# MCU.net
KiCad netlist of a schematic drawn in Altium Designer
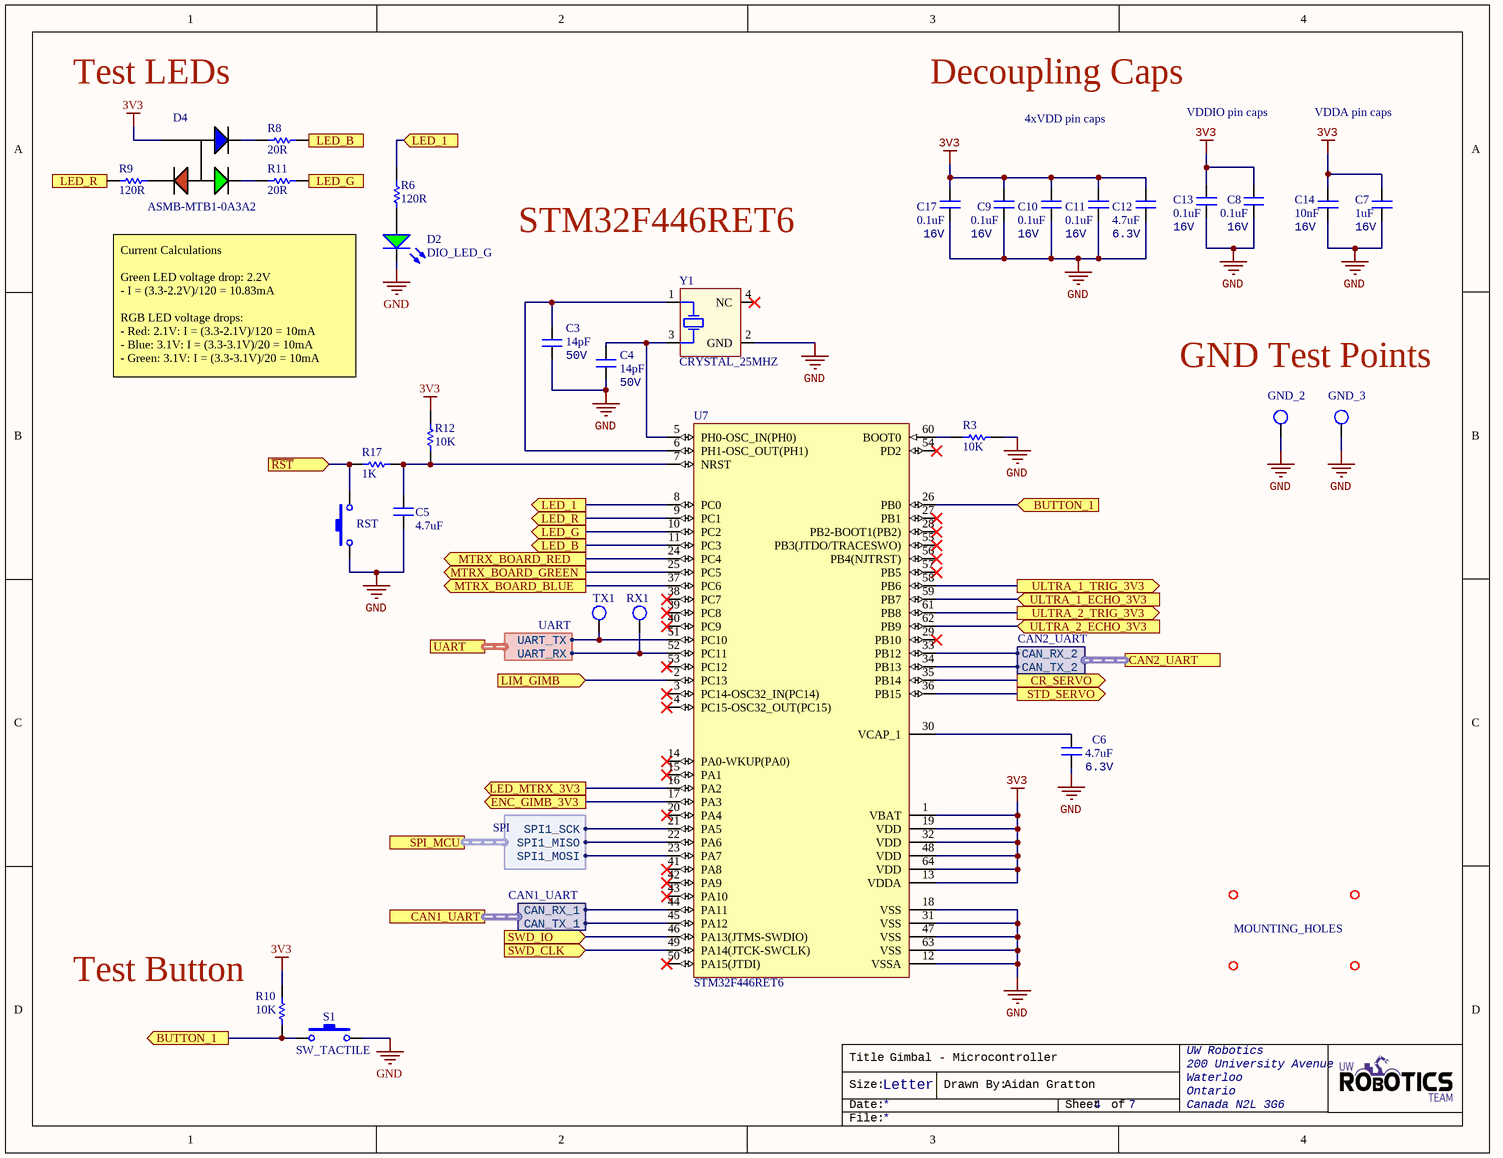
[diagram p0: MCU.SchDoc]

(export (version "E")
  (design (tool "Eeschema 10.0.6"))
  (components
    (comp (ref "C3")
      (value "14pF")
      (footprint "CAPC0603(1608)55_N")
      (description "Cap Ceramic 14pF 50V C0G 5% SMD 0603 125C Cardboard T/R")
      (fields
        (field (name "TOLERANCE") "5%")
        (field (name "VOLTAGE RATING (DC)") "50V")
        (field (name "Comment") "CL10C140JB8NNNC")
      )
      (libsource (lib "UWRT_Schematic_Library_2020") (part "CL10C140JB8NNNC"))
    )
    (comp (ref "C4")
      (value "14pF")
      (footprint "CAPC0603(1608)55_N")
      (description "Cap Ceramic 14pF 50V C0G 5% SMD 0603 125C Cardboard T/R")
      (fields
        (field (name "TOLERANCE") "5%")
        (field (name "VOLTAGE RATING (DC)") "50V")
        (field (name "Comment") "CL10C140JB8NNNC")
      )
      (libsource (lib "UWRT_Schematic_Library_2020") (part "CL10C140JB8NNNC"))
    )
    (comp (ref "C5")
      (value "4.7uF")
      (footprint "CAPC0603(1608)55_N")
      (description "CAP CER 4.7UF 6.3V X5R 0603")
      (fields (field (name "Comment") "CAP_4.7uF_0603"))
      (libsource (lib "UWRT_Schematic_Library_2020") (part "CAP_4.7uF_0603"))
    )
    (comp (ref "C6")
      (value "4.7uF")
      (footprint "CAPC0603(1608)55_N")
      (description "CAP CER 4.7UF 6.3V X5R 0603")
      (fields
        (field (name "MANUFACTURER") "Yageo")
        (field (name "VOLTAGE RATING") "6.3V")
        (field (name "MPN") "CC0603KRX5R5BB475")
      )
      (libsource (lib "UWRT_Schematic_Library_2020") (part "CAP_4.7uF_0603"))
    )
    (comp (ref "C7")
      (value "1uF")
      (footprint "CAPC0603(1608)55_N")
      (description "CAP CER 1UF 16V Y5V 0603")
      (fields
        (field (name "MANUFACTURER") "Yageo")
        (field (name "VOLTAGE RATING") "16V")
        (field (name "MPN") "CC0603ZRY5V7BB105")
      )
      (libsource (lib "UWRT_Schematic_Library_2020") (part "CAP_1uF_16V_0603"))
    )
    (comp (ref "C8")
      (value "0.1uF")
      (footprint "CAPC0603(1608)55_N")
      (description "CAP CER 0.1UF 16V X7R 0603")
      (fields
        (field (name "MANUFACTURER") "Yageo")
        (field (name "VOLTAGE RATING") "16V")
        (field (name "MPN") "CC0603KRX7R7BB104")
      )
      (libsource (lib "UWRT_Schematic_Library_2020") (part "CAP_0.1uF_16V_0603"))
    )
    (comp (ref "C9")
      (value "0.1uF")
      (footprint "CAPC0603(1608)55_N")
      (description "CAP CER 0.1UF 16V X7R 0603")
      (fields
        (field (name "MANUFACTURER") "Yageo")
        (field (name "VOLTAGE RATING") "16V")
        (field (name "MPN") "CC0603KRX7R7BB104")
      )
      (libsource (lib "UWRT_Schematic_Library_2020") (part "CAP_0.1uF_16V_0603"))
    )
    (comp (ref "C10")
      (value "0.1uF")
      (footprint "CAPC0603(1608)55_N")
      (description "CAP CER 0.1UF 16V X7R 0603")
      (fields
        (field (name "MANUFACTURER") "Yageo")
        (field (name "VOLTAGE RATING") "16V")
        (field (name "MPN") "CC0603KRX7R7BB104")
      )
      (libsource (lib "UWRT_Schematic_Library_2020") (part "CAP_0.1uF_16V_0603"))
    )
    (comp (ref "C11")
      (value "0.1uF")
      (footprint "CAPC0603(1608)55_N")
      (description "CAP CER 0.1UF 16V X7R 0603")
      (fields
        (field (name "MANUFACTURER") "Yageo")
        (field (name "VOLTAGE RATING") "16V")
        (field (name "MPN") "CC0603KRX7R7BB104")
      )
      (libsource (lib "UWRT_Schematic_Library_2020") (part "CAP_0.1uF_16V_0603"))
    )
    (comp (ref "C12")
      (value "4.7uF")
      (footprint "CAPC0603(1608)55_N")
      (description "CAP CER 4.7UF 6.3V X5R 0603")
      (fields
        (field (name "MANUFACTURER") "Yageo")
        (field (name "VOLTAGE RATING") "6.3V")
        (field (name "MPN") "CC0603KRX5R5BB475")
      )
      (libsource (lib "UWRT_Schematic_Library_2020") (part "CAP_4.7uF_0603"))
    )
    (comp (ref "C13")
      (value "0.1uF")
      (footprint "CAPC0603(1608)55_N")
      (description "CAP CER 0.1UF 16V X7R 0603")
      (fields
        (field (name "MANUFACTURER") "Yageo")
        (field (name "VOLTAGE RATING") "16V")
        (field (name "MPN") "CC0603KRX7R7BB104")
      )
      (libsource (lib "UWRT_Schematic_Library_2020") (part "CAP_0.1uF_16V_0603"))
    )
    (comp (ref "C14")
      (value "10nF")
      (footprint "CAPC0603(1608)55_N")
      (description "CAP CER 10000PF 16V X7R 0603")
      (fields
        (field (name "MANUFACTURER") "Yageo")
        (field (name "VOLTAGE RATING") "16V")
        (field (name "MPN") "CC0603KRX7R7BB103")
      )
      (libsource (lib "UWRT_Schematic_Library_2020") (part "CAP_10nF_0603"))
    )
    (comp (ref "C17")
      (value "0.1uF")
      (footprint "CAPC0603(1608)55_N")
      (description "CAP CER 0.1UF 16V X7R 0603")
      (fields
        (field (name "MANUFACTURER") "Yageo")
        (field (name "VOLTAGE RATING") "16V")
        (field (name "MPN") "CC0603KRX7R7BB104")
      )
      (libsource (lib "UWRT_Schematic_Library_2020") (part "CAP_0.1uF_16V_0603"))
    )
    (comp (ref "D2")
      (value "DIO_LED_G")
      (footprint "LED_0805_LINE")
      (description "LED GREEN DIFFUSED 0805 SMD")
      (fields (field (name "MANUFACTURER") "OSRAM") (field (name "MPN") "LG R971-KN-1"))
      (libsource (lib "UWRT_Schematic_Library_2020") (part "DIO_LED_G"))
    )
    (comp (ref "D4")
      (value "LED_RGB")
      (footprint "LED_RGB")
      (description "LED RGB DIFFUSED 4PLCC SMD")
      (fields (field (name "MANUFACTURER PART NUMBER 1") "ASMB-MTB1-0A3A2"))
      (libsource (lib "UWRT_Schematic_Library_2020") (part "LED_RGB"))
    )
    (comp (ref "GND_2")
      (value "TESTPOINT_LOOP")
      (footprint "TESTPOINT_LOOP")
      (description "Loop testpoint through-hole pad")
      (fields (field (name "MANUFACTURER") "Keystone Electronics"))
      (libsource (lib "UWRT_Schematic_Library_2020") (part "TESTPOINT_LOOP"))
    )
    (comp (ref "GND_3")
      (value "TESTPOINT_LOOP")
      (footprint "TESTPOINT_LOOP")
      (description "Loop testpoint through-hole pad")
      (fields (field (name "MANUFACTURER") "Keystone Electronics"))
      (libsource (lib "UWRT_Schematic_Library_2020") (part "TESTPOINT_LOOP"))
    )
    (comp (ref "MH1")
      (value "MOUNTING_HOLES")
      (footprint "MOUNTING_HOLE")
      (description "6cm x 6cm")
      (libsource (lib "UWRT_Schematic_Library_2020") (part "MOUNTING_HOLES"))
    )
    (comp (ref "MH2")
      (value "MOUNTING_HOLES")
      (footprint "MOUNTING_HOLE")
      (description "6cm x 6cm")
      (libsource (lib "UWRT_Schematic_Library_2020") (part "MOUNTING_HOLES"))
    )
    (comp (ref "MH3")
      (value "MOUNTING_HOLES")
      (footprint "MOUNTING_HOLE")
      (description "6cm x 6cm")
      (libsource (lib "UWRT_Schematic_Library_2020") (part "MOUNTING_HOLES"))
    )
    (comp (ref "MH4")
      (value "MOUNTING_HOLES")
      (footprint "MOUNTING_HOLE")
      (description "6cm x 6cm")
      (libsource (lib "UWRT_Schematic_Library_2020") (part "MOUNTING_HOLES"))
    )
    (comp (ref "R3")
      (value "10K")
      (footprint "RESC0603(1608)_N")
      (description "RES SMD 10K OHM 5% 1/10W 0603")
      (fields (field (name "MANUFACTURER") "Yageo") (field (name "MPN") "RC0603JR-0710KL"))
      (libsource (lib "UWRT_Schematic_Library_2020") (part "RES_10K_0603"))
    )
    (comp (ref "R6")
      (value "120R")
      (footprint "RESC0603(1608)_N")
      (description "RES SMD 120 OHM 5% 1/10W 0603")
      (fields (field (name "MANUFACTURER") "Yageo") (field (name "MPN") "RC0603JR-07120RL"))
      (libsource (lib "UWRT_Schematic_Library_2020") (part "RES_120R_0603"))
    )
    (comp (ref "R8")
      (value "20R")
      (footprint "RESC0603(1608)_N")
      (description "RES SMD 20 OHM 5% 1/10W 0603")
      (fields (field (name "MANUFACTURER") "Yageo") (field (name "MPN") "RC0603JR-0720RL"))
      (libsource (lib "UWRT_Schematic_Library_2020") (part "RES_20R_0603"))
    )
    (comp (ref "R9")
      (value "120R")
      (footprint "RESC0603(1608)_N")
      (description "RES SMD 120 OHM 5% 1/10W 0603")
      (fields (field (name "MANUFACTURER") "Yageo") (field (name "MPN") "RC0603JR-07120RL"))
      (libsource (lib "UWRT_Schematic_Library_2020") (part "RES_120R_0603"))
    )
    (comp (ref "R10")
      (value "10K")
      (footprint "RESC0603(1608)_N")
      (description "RES SMD 10K OHM 5% 1/10W 0603")
      (fields (field (name "MANUFACTURER") "Yageo") (field (name "TOLERANCE") "5%"))
      (libsource (lib "UWRT_Schematic_Library_2020") (part "RES_10K_0603"))
    )
    (comp (ref "R11")
      (value "20R")
      (footprint "RESC0603(1608)_N")
      (description "RES SMD 20 OHM 5% 1/10W 0603")
      (fields (field (name "MANUFACTURER") "Yageo") (field (name "MPN") "RC0603JR-0720RL"))
      (libsource (lib "UWRT_Schematic_Library_2020") (part "RES_20R_0603"))
    )
    (comp (ref "R12")
      (value "10K")
      (footprint "RESC0603(1608)_N")
      (description "RES SMD 10K OHM 5% 1/10W 0603")
      (fields (field (name "MANUFACTURER") "Yageo") (field (name "MPN") "RC0603JR-0710KL"))
      (libsource (lib "UWRT_Schematic_Library_2020") (part "RES_10K_0603"))
    )
    (comp (ref "R17")
      (value "1K")
      (footprint "RESC0603(1608)_N")
      (description "RES SMD 1K OHM 5% 1/10W 0603")
      (fields (field (name "TOLERANCE") "5%") (field (name "Comment") "RES_1K_0603"))
      (libsource (lib "UWRT_Schematic_Library_2020") (part "RES_1K_0603"))
    )
    (comp (ref "RST")
      (value "SW_PWR")
      (footprint "PTS830GM140")
      (description "Power Switch (Red)")
      (fields (field (name "MPN") "PTS830GM140 SMTR LFS") (field (name "MANUFACTURER") "C&K"))
      (libsource (lib "UWRT_Schematic_Library_2020") (part "SW_PWR"))
    )
    (comp (ref "RX1")
      (value "TESTPOINT_LOOP")
      (footprint "TESTPOINT_LOOP")
      (description "Loop testpoint through-hole pad")
      (fields (field (name "MANUFACTURER") "Keystone Electronics"))
      (libsource (lib "UWRT_Schematic_Library_2020") (part "TESTPOINT_LOOP"))
    )
    (comp (ref "S1")
      (value "SW_TACTILE")
      (footprint "B3U-1100P")
      (description "Tactile Switch (Grey)")
      (fields (field (name "MPN") "B3U-1100P") (field (name "MANUFACTURER") "Omron Electronics Inc-EMC Div"))
      (libsource (lib "UWRT_Schematic_Library_2020") (part "SW_TACTILE"))
    )
    (comp (ref "TX1")
      (value "TESTPOINT_LOOP")
      (footprint "TESTPOINT_LOOP")
      (description "Loop testpoint through-hole pad")
      (fields (field (name "MANUFACTURER") "Keystone Electronics"))
      (libsource (lib "UWRT_Schematic_Library_2020") (part "TESTPOINT_LOOP"))
    )
    (comp (ref "U7")
      (value "STM32F446RET6")
      (footprint "STM-LQFP64_L")
      (libsource (lib "UWRT_Schematic_Library_2020") (part "MCU_STM32F446RET6"))
    )
    (comp (ref "Y1")
      (value "CRYSTAL_25MHZ")
      (footprint "AVX-CX2520DB32000D0GEJZ1-4_V")
      (description "CRYSTAL 25.0000MHZ 12PF SMD")
      (libsource (lib "UWRT_Schematic_Library_2020") (part "CRYSTAL_25MHZ"))
    )
  )
  (nets
    (net (code "5") (name "/BUTTON_1") (class "Default")
      (node (ref "R10") (pin "2") (pinfunction "2_2") (pintype "passive"))
      (node (ref "S1") (pin "1") (pinfunction "1_1") (pintype "passive"))
      (node (ref "U7") (pin "26") (pinfunction "PB0_26") (pintype "bidirectional"))
    )
    (net (code "6") (name "/CAN_RX_1") (class "Default")
      (node (ref "U7") (pin "44") (pinfunction "PA11_44") (pintype "bidirectional"))
    )
    (net (code "7") (name "/CAN_RX_2") (class "Default")
      (node (ref "U7") (pin "33") (pinfunction "PB12_33") (pintype "bidirectional"))
    )
    (net (code "8") (name "/CAN_TX_1") (class "Default")
      (node (ref "U7") (pin "45") (pinfunction "PA12_45") (pintype "bidirectional"))
    )
    (net (code "9") (name "/CAN_TX_2") (class "Default")
      (node (ref "U7") (pin "34") (pinfunction "PB13_34") (pintype "bidirectional"))
    )
    (net (code "10") (name "/CR_SERVO") (class "Default")
      (node (ref "U7") (pin "35") (pinfunction "PB14_35") (pintype "bidirectional"))
    )
    (net (code "11") (name "/ENC_GIMB_3V3") (class "Default")
      (node (ref "U7") (pin "17") (pinfunction "PA3_17") (pintype "bidirectional"))
    )
    (net (code "12") (name "/LED_1") (class "Default")
      (node (ref "R6") (pin "1") (pinfunction "1_1") (pintype "passive"))
      (node (ref "U7") (pin "8") (pinfunction "PC0_8") (pintype "bidirectional"))
    )
    (net (code "13") (name "/LED_B") (class "Default")
      (node (ref "R8") (pin "2") (pinfunction "2_2") (pintype "passive"))
      (node (ref "U7") (pin "11") (pinfunction "PC3_11") (pintype "bidirectional"))
    )
    (net (code "14") (name "/LED_G") (class "Default")
      (node (ref "R11") (pin "2") (pinfunction "2_2") (pintype "passive"))
      (node (ref "U7") (pin "10") (pinfunction "PC2_10") (pintype "bidirectional"))
    )
    (net (code "15") (name "/LED_MTRX_3V3") (class "Default")
      (node (ref "U7") (pin "16") (pinfunction "PA2_16") (pintype "bidirectional"))
    )
    (net (code "16") (name "/LED_R") (class "Default")
      (node (ref "R9") (pin "1") (pinfunction "1_1") (pintype "passive"))
      (node (ref "U7") (pin "9") (pinfunction "PC1_9") (pintype "bidirectional"))
    )
    (net (code "17") (name "/LIM_GIMB") (class "Default")
      (node (ref "U7") (pin "2") (pinfunction "PC13_2") (pintype "bidirectional"))
    )
    (net (code "18") (name "/MTRX_BOARD_BLUE") (class "Default")
      (node (ref "U7") (pin "37") (pinfunction "PC6_37") (pintype "bidirectional"))
    )
    (net (code "19") (name "/MTRX_BOARD_GREEN") (class "Default")
      (node (ref "U7") (pin "25") (pinfunction "PC5_25") (pintype "bidirectional"))
    )
    (net (code "20") (name "/MTRX_BOARD_RED") (class "Default")
      (node (ref "U7") (pin "24") (pinfunction "PC4_24") (pintype "bidirectional"))
    )
    (net (code "21") (name "/SPI1_MISO") (class "Default")
      (node (ref "U7") (pin "22") (pinfunction "PA6_22") (pintype "bidirectional"))
    )
    (net (code "22") (name "/SPI1_MOSI") (class "Default")
      (node (ref "U7") (pin "23") (pinfunction "PA7_23") (pintype "bidirectional"))
    )
    (net (code "23") (name "/SPI1_SCK") (class "Default")
      (node (ref "U7") (pin "21") (pinfunction "PA5_21") (pintype "bidirectional"))
    )
    (net (code "24") (name "/STD_SERVO") (class "Default")
      (node (ref "U7") (pin "36") (pinfunction "PB15_36") (pintype "bidirectional"))
    )
    (net (code "25") (name "/SWD_CLK") (class "Default")
      (node (ref "U7") (pin "49") (pinfunction "PA14(JTCK-SWCLK)_49") (pintype "bidirectional"))
    )
    (net (code "26") (name "/SWD_IO") (class "Default")
      (node (ref "U7") (pin "46") (pinfunction "PA13(JTMS-SWDIO)_46") (pintype "bidirectional"))
    )
    (net (code "27") (name "/UART_RX") (class "Default")
      (node (ref "RX1") (pin "1") (pintype "passive"))
      (node (ref "U7") (pin "52") (pinfunction "PC11_52") (pintype "bidirectional"))
    )
    (net (code "28") (name "/UART_TX") (class "Default")
      (node (ref "TX1") (pin "1") (pintype "passive"))
      (node (ref "U7") (pin "51") (pinfunction "PC10_51") (pintype "bidirectional"))
    )
    (net (code "29") (name "/ULTRA_1_ECHO_3V3") (class "Default")
      (node (ref "U7") (pin "59") (pinfunction "PB7_59") (pintype "bidirectional"))
    )
    (net (code "30") (name "/ULTRA_1_TRIG_3V3") (class "Default")
      (node (ref "U7") (pin "58") (pinfunction "PB6_58") (pintype "bidirectional"))
    )
    (net (code "31") (name "/ULTRA_2_ECHO_3V3") (class "Default")
      (node (ref "U7") (pin "62") (pinfunction "PB9_62") (pintype "bidirectional"))
    )
    (net (code "32") (name "/ULTRA_2_TRIG_3V3") (class "Default")
      (node (ref "U7") (pin "61") (pinfunction "PB8_61") (pintype "bidirectional"))
    )
    (net (code "37") (name "/~{RST}") (class "Default")
      (node (ref "R17") (pin "1") (pinfunction "1_1") (pintype "passive"))
      (node (ref "RST") (pin "2") (pinfunction "2_2") (pintype "passive"))
    )
    (net (code "38") (name "3V3") (class "Default")
      (node (ref "C10") (pin "2") (pinfunction "2_2") (pintype "passive"))
      (node (ref "C11") (pin "2") (pinfunction "2_2") (pintype "passive"))
      (node (ref "C12") (pin "2") (pinfunction "2_2") (pintype "passive"))
      (node (ref "C13") (pin "2") (pinfunction "2_2") (pintype "passive"))
      (node (ref "C14") (pin "2") (pinfunction "2_2") (pintype "passive"))
      (node (ref "C17") (pin "2") (pinfunction "2_2") (pintype "passive"))
      (node (ref "C7") (pin "2") (pinfunction "2_2") (pintype "passive"))
      (node (ref "C8") (pin "2") (pinfunction "2_2") (pintype "passive"))
      (node (ref "C9") (pin "2") (pinfunction "2_2") (pintype "passive"))
      (node (ref "D4") (pin "4") (pinfunction "9_4") (pintype "passive"))
      (node (ref "R10") (pin "1") (pinfunction "1_1") (pintype "passive"))
      (node (ref "R12") (pin "2") (pinfunction "2_2") (pintype "passive"))
      (node (ref "U7") (pin "1") (pinfunction "VBAT_1") (pintype "power_in"))
      (node (ref "U7") (pin "13") (pinfunction "VDDA_13") (pintype "power_in"))
      (node (ref "U7") (pin "19") (pinfunction "VDD_19") (pintype "power_in"))
      (node (ref "U7") (pin "32") (pinfunction "VDD_32") (pintype "power_in"))
      (node (ref "U7") (pin "48") (pinfunction "VDD_48") (pintype "power_in"))
      (node (ref "U7") (pin "64") (pinfunction "VDD_64") (pintype "power_in"))
    )
    (net (code "39") (name "GND") (class "Default")
      (node (ref "C10") (pin "1") (pinfunction "1_1") (pintype "passive"))
      (node (ref "C11") (pin "1") (pinfunction "1_1") (pintype "passive"))
      (node (ref "C12") (pin "1") (pinfunction "1_1") (pintype "passive"))
      (node (ref "C13") (pin "1") (pinfunction "1_1") (pintype "passive"))
      (node (ref "C14") (pin "1") (pinfunction "1_1") (pintype "passive"))
      (node (ref "C17") (pin "1") (pinfunction "1_1") (pintype "passive"))
      (node (ref "C3") (pin "1") (pinfunction "1_1") (pintype "passive"))
      (node (ref "C4") (pin "1") (pinfunction "1_1") (pintype "passive"))
      (node (ref "C5") (pin "1") (pinfunction "1_1") (pintype "passive"))
      (node (ref "C6") (pin "1") (pinfunction "1_1") (pintype "passive"))
      (node (ref "C7") (pin "1") (pinfunction "1_1") (pintype "passive"))
      (node (ref "C8") (pin "1") (pinfunction "1_1") (pintype "passive"))
      (node (ref "C9") (pin "1") (pinfunction "1_1") (pintype "passive"))
      (node (ref "D2") (pin "2") (pinfunction "K_2") (pintype "passive"))
      (node (ref "GND_2") (pin "1") (pintype "passive"))
      (node (ref "GND_3") (pin "1") (pintype "passive"))
      (node (ref "R3") (pin "2") (pinfunction "2_2") (pintype "passive"))
      (node (ref "RST") (pin "1") (pinfunction "1_1") (pintype "passive"))
      (node (ref "S1") (pin "2") (pinfunction "2_2") (pintype "passive"))
      (node (ref "U7") (pin "12") (pinfunction "VSSA_12") (pintype "power_in"))
      (node (ref "U7") (pin "18") (pinfunction "VSS_18") (pintype "power_in"))
      (node (ref "U7") (pin "31") (pinfunction "VSS_31") (pintype "power_in"))
      (node (ref "U7") (pin "47") (pinfunction "VSS_47") (pintype "power_in"))
      (node (ref "U7") (pin "63") (pinfunction "VSS_63") (pintype "power_in"))
      (node (ref "Y1") (pin "2") (pinfunction "GND_2") (pintype "power_in"))
    )
    (net (code "40") (name "Net-(D2-A)") (class "Default")
      (node (ref "D2") (pin "1") (pinfunction "A_1") (pintype "passive"))
      (node (ref "R6") (pin "2") (pinfunction "2_2") (pintype "passive"))
    )
    (net (code "41") (name "Net-(D4-10)") (class "Default")
      (node (ref "D4") (pin "3") (pinfunction "10_3") (pintype "passive"))
      (node (ref "R8") (pin "1") (pinfunction "1_1") (pintype "passive"))
    )
    (net (code "42") (name "Net-(D4-11)") (class "Default")
      (node (ref "D4") (pin "1") (pinfunction "11_1") (pintype "passive"))
      (node (ref "R9") (pin "2") (pinfunction "2_2") (pintype "passive"))
    )
    (net (code "43") (name "Net-(D4-12)") (class "Default")
      (node (ref "D4") (pin "2") (pinfunction "12_2") (pintype "passive"))
      (node (ref "R11") (pin "1") (pinfunction "1_1") (pintype "passive"))
    )
    (net (code "44") (name "Net-(U7-BOOT0)") (class "Default")
      (node (ref "R3") (pin "1") (pinfunction "1_1") (pintype "passive"))
      (node (ref "U7") (pin "60") (pinfunction "BOOT0_60") (pintype "input"))
    )
    (net (code "45") (name "Net-(U7-NRST)") (class "Default")
      (node (ref "C5") (pin "2") (pinfunction "2_2") (pintype "passive"))
      (node (ref "R12") (pin "1") (pinfunction "1_1") (pintype "passive"))
      (node (ref "R17") (pin "2") (pinfunction "2_2") (pintype "passive"))
      (node (ref "U7") (pin "7") (pinfunction "NRST_7") (pintype "bidirectional"))
    )
    (net (code "46") (name "Net-(U7-PH0-OSC_IN(PH0))") (class "Default")
      (node (ref "C4") (pin "2") (pinfunction "2_2") (pintype "passive"))
      (node (ref "U7") (pin "5") (pinfunction "PH0-OSC_IN(PH0)_5") (pintype "bidirectional"))
      (node (ref "Y1") (pin "3") (pinfunction "HOT_3") (pintype "passive"))
    )
    (net (code "47") (name "Net-(U7-PH1-OSC_OUT(PH1))") (class "Default")
      (node (ref "C3") (pin "2") (pinfunction "2_2") (pintype "passive"))
      (node (ref "U7") (pin "6") (pinfunction "PH1-OSC_OUT(PH1)_6") (pintype "bidirectional"))
      (node (ref "Y1") (pin "1") (pinfunction "HOT_1") (pintype "passive"))
    )
    (net (code "48") (name "Net-(U7-VCAP_1)") (class "Default")
      (node (ref "C6") (pin "2") (pinfunction "2_2") (pintype "passive"))
      (node (ref "U7") (pin "30") (pinfunction "VCAP_1_30") (pintype "passive"))
    )
    (net (code "49") (name "unconnected-(U7-PA0-WKUP(PA0)-Pad14)") (class "Default")
      (node (ref "U7") (pin "14") (pinfunction "PA0-WKUP(PA0)_14") (pintype "bidirectional+no_connect"))
    )
    (net (code "50") (name "unconnected-(U7-PA1-Pad15)") (class "Default")
      (node (ref "U7") (pin "15") (pinfunction "PA1_15") (pintype "bidirectional+no_connect"))
    )
    (net (code "51") (name "unconnected-(U7-PA4-Pad20)") (class "Default")
      (node (ref "U7") (pin "20") (pinfunction "PA4_20") (pintype "bidirectional+no_connect"))
    )
    (net (code "52") (name "unconnected-(U7-PA8-Pad41)") (class "Default")
      (node (ref "U7") (pin "41") (pinfunction "PA8_41") (pintype "bidirectional+no_connect"))
    )
    (net (code "53") (name "unconnected-(U7-PA9-Pad42)") (class "Default")
      (node (ref "U7") (pin "42") (pinfunction "PA9_42") (pintype "bidirectional+no_connect"))
    )
    (net (code "54") (name "unconnected-(U7-PA10-Pad43)") (class "Default")
      (node (ref "U7") (pin "43") (pinfunction "PA10_43") (pintype "bidirectional+no_connect"))
    )
    (net (code "55") (name "unconnected-(U7-PA15(JTDI)-Pad50)") (class "Default")
      (node (ref "U7") (pin "50") (pinfunction "PA15(JTDI)_50") (pintype "bidirectional+no_connect"))
    )
    (net (code "56") (name "unconnected-(U7-PB1-Pad27)") (class "Default")
      (node (ref "U7") (pin "27") (pinfunction "PB1_27") (pintype "bidirectional+no_connect"))
    )
    (net (code "57") (name "unconnected-(U7-PB2-BOOT1(PB2)-Pad28)") (class "Default")
      (node (ref "U7") (pin "28") (pinfunction "PB2-BOOT1(PB2)_28") (pintype "bidirectional+no_connect"))
    )
    (net (code "58") (name "unconnected-(U7-PB3(JTDO{slash}TRACESWO)-Pad55)") (class "Default")
      (node (ref "U7") (pin "55") (pinfunction "PB3(JTDO/TRACESWO)_55") (pintype "bidirectional+no_connect"))
    )
    (net (code "59") (name "unconnected-(U7-PB4(NJTRST)-Pad56)") (class "Default")
      (node (ref "U7") (pin "56") (pinfunction "PB4(NJTRST)_56") (pintype "bidirectional+no_connect"))
    )
    (net (code "60") (name "unconnected-(U7-PB5-Pad57)") (class "Default")
      (node (ref "U7") (pin "57") (pinfunction "PB5_57") (pintype "bidirectional+no_connect"))
    )
    (net (code "61") (name "unconnected-(U7-PB10-Pad29)") (class "Default")
      (node (ref "U7") (pin "29") (pinfunction "PB10_29") (pintype "bidirectional+no_connect"))
    )
    (net (code "62") (name "unconnected-(U7-PC7-Pad38)") (class "Default")
      (node (ref "U7") (pin "38") (pinfunction "PC7_38") (pintype "bidirectional+no_connect"))
    )
    (net (code "63") (name "unconnected-(U7-PC8-Pad39)") (class "Default")
      (node (ref "U7") (pin "39") (pinfunction "PC8_39") (pintype "bidirectional+no_connect"))
    )
    (net (code "64") (name "unconnected-(U7-PC9-Pad40)") (class "Default")
      (node (ref "U7") (pin "40") (pinfunction "PC9_40") (pintype "bidirectional+no_connect"))
    )
    (net (code "65") (name "unconnected-(U7-PC12-Pad53)") (class "Default")
      (node (ref "U7") (pin "53") (pinfunction "PC12_53") (pintype "bidirectional+no_connect"))
    )
    (net (code "66") (name "unconnected-(U7-PC14-OSC32_IN(PC14)-Pad3)") (class "Default")
      (node (ref "U7") (pin "3") (pinfunction "PC14-OSC32_IN(PC14)_3") (pintype "bidirectional+no_connect"))
    )
    (net (code "67") (name "unconnected-(U7-PC15-OSC32_OUT(PC15)-Pad4)") (class "Default")
      (node (ref "U7") (pin "4") (pinfunction "PC15-OSC32_OUT(PC15)_4") (pintype "bidirectional+no_connect"))
    )
    (net (code "68") (name "unconnected-(U7-PD2-Pad54)") (class "Default")
      (node (ref "U7") (pin "54") (pinfunction "PD2_54") (pintype "bidirectional+no_connect"))
    )
    (net (code "69") (name "unconnected-(Y1-NC-Pad4)") (class "Default")
      (node (ref "Y1") (pin "4") (pinfunction "NC_4") (pintype "passive+no_connect"))
    )
  )
)
